# TopLevel.net
KiCad netlist of a schematic drawn in Altium Designer
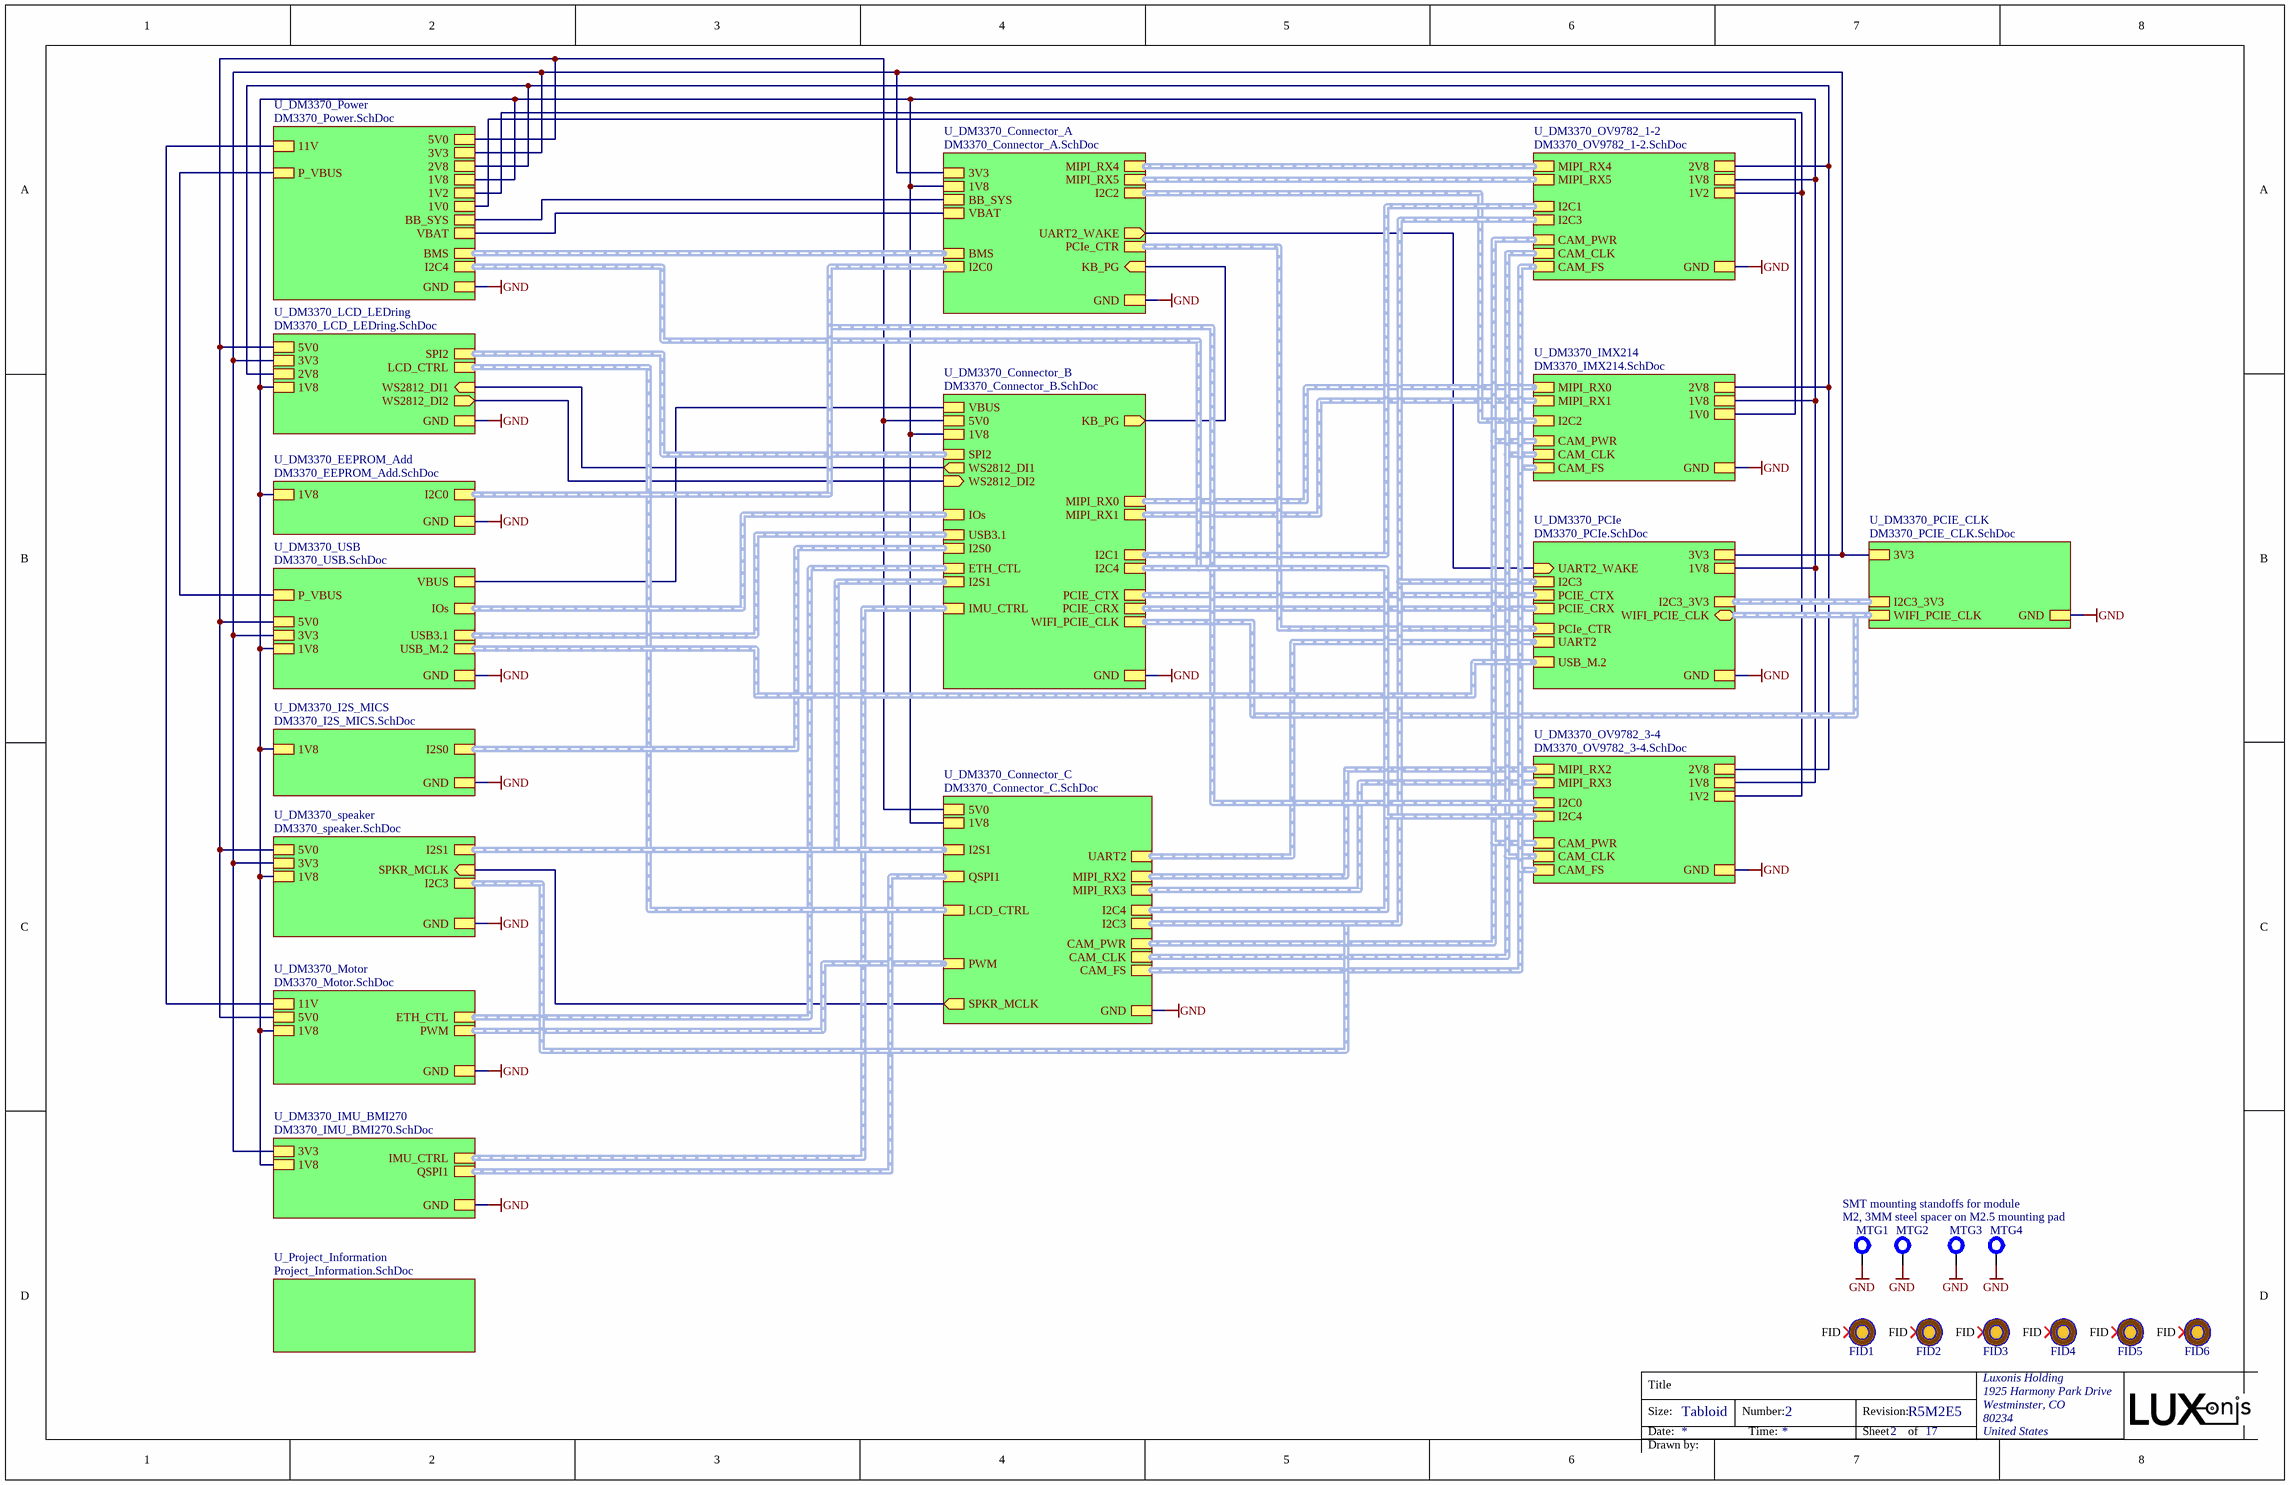
[diagram p0: TopLevel.SchDoc]

(export (version "E")
  (design (tool "Eeschema 10.0.6"))
  (components
    (comp (ref "FID1")
      (value "FIDUCIAL_ROUND_1MM")
      (footprint "LuxonisMaster:FIDUCIAL_ROUND_1MM")
      (description "Fiducial with various available footprints")
      (libsource (lib "LuxonisMaster") (part "FIDUCIAL"))
    )
    (comp (ref "FID2")
      (value "FIDUCIAL_ROUND_1MM")
      (footprint "LuxonisMaster:FIDUCIAL_ROUND_1MM")
      (description "Fiducial with various available footprints")
      (libsource (lib "LuxonisMaster") (part "FIDUCIAL"))
    )
    (comp (ref "FID3")
      (value "FIDUCIAL_ROUND_1MM")
      (footprint "LuxonisMaster:FIDUCIAL_ROUND_1MM")
      (description "Fiducial with various available footprints")
      (libsource (lib "LuxonisMaster") (part "FIDUCIAL"))
    )
    (comp (ref "FID4")
      (value "FIDUCIAL_ROUND_1MM")
      (footprint "LuxonisMaster:FIDUCIAL_ROUND_1MM")
      (description "Fiducial with various available footprints")
      (libsource (lib "LuxonisMaster") (part "FIDUCIAL"))
    )
    (comp (ref "FID5")
      (value "FIDUCIAL_ROUND_1MM")
      (footprint "LuxonisMaster:FIDUCIAL_ROUND_1MM")
      (description "Fiducial with various available footprints")
      (libsource (lib "LuxonisMaster") (part "FIDUCIAL"))
    )
    (comp (ref "FID6")
      (value "FIDUCIAL_ROUND_1MM")
      (footprint "LuxonisMaster:FIDUCIAL_ROUND_1MM")
      (description "Fiducial with various available footprints")
      (libsource (lib "LuxonisMaster") (part "FIDUCIAL"))
    )
    (comp (ref "MTG1")
      (value "M2, 3MM steel spacer on M2.5 mounting pad")
      (footprint "LuxonisMaster:9774030243R")
      (description "MP ROUND STANDOFF M2X0.4 STEEL 3MM")
      (libsource (lib "LuxonisMaster") (part "9774030243R"))
    )
    (comp (ref "MTG2")
      (value "M2, 3MM steel spacer on M2.5 mounting pad")
      (footprint "LuxonisMaster:9774030243R")
      (description "MP ROUND STANDOFF M2X0.4 STEEL 3MM")
      (libsource (lib "LuxonisMaster") (part "9774030243R"))
    )
    (comp (ref "MTG3")
      (value "M2, 3MM steel spacer on M2.5 mounting pad")
      (footprint "LuxonisMaster:9774030243R")
      (description "MP ROUND STANDOFF M2X0.4 STEEL 3MM")
      (libsource (lib "LuxonisMaster") (part "9774030243R"))
    )
    (comp (ref "MTG4")
      (value "M2, 3MM steel spacer on M2.5 mounting pad")
      (footprint "LuxonisMaster:9774030243R")
      (description "MP ROUND STANDOFF M2X0.4 STEEL 3MM")
      (libsource (lib "LuxonisMaster") (part "9774030243R"))
    )
  )
  (nets
    (net (code "49") (name "GND") (class "Default")
      (node (ref "MTG1") (pin "1") (pintype "passive"))
      (node (ref "MTG2") (pin "1") (pintype "passive"))
      (node (ref "MTG3") (pin "1") (pintype "passive"))
      (node (ref "MTG4") (pin "1") (pintype "passive"))
    )
    (net (code "50") (name "unconnected-(FID1-PadFID)") (class "Default")
      (node (ref "FID1") (pin "FID") (pinfunction "FID_FID") (pintype "input+no_connect"))
    )
    (net (code "51") (name "unconnected-(FID2-PadFID)") (class "Default")
      (node (ref "FID2") (pin "FID") (pinfunction "FID_FID") (pintype "input+no_connect"))
    )
    (net (code "52") (name "unconnected-(FID3-PadFID)") (class "Default")
      (node (ref "FID3") (pin "FID") (pinfunction "FID_FID") (pintype "input+no_connect"))
    )
    (net (code "53") (name "unconnected-(FID4-PadFID)") (class "Default")
      (node (ref "FID4") (pin "FID") (pinfunction "FID_FID") (pintype "input+no_connect"))
    )
    (net (code "54") (name "unconnected-(FID5-PadFID)") (class "Default")
      (node (ref "FID5") (pin "FID") (pinfunction "FID_FID") (pintype "input+no_connect"))
    )
    (net (code "55") (name "unconnected-(FID6-PadFID)") (class "Default")
      (node (ref "FID6") (pin "FID") (pinfunction "FID_FID") (pintype "input+no_connect"))
    )
  )
)
